# amp_soha_v4.net
KiCad netlist of a schematic drawn in EAGLE
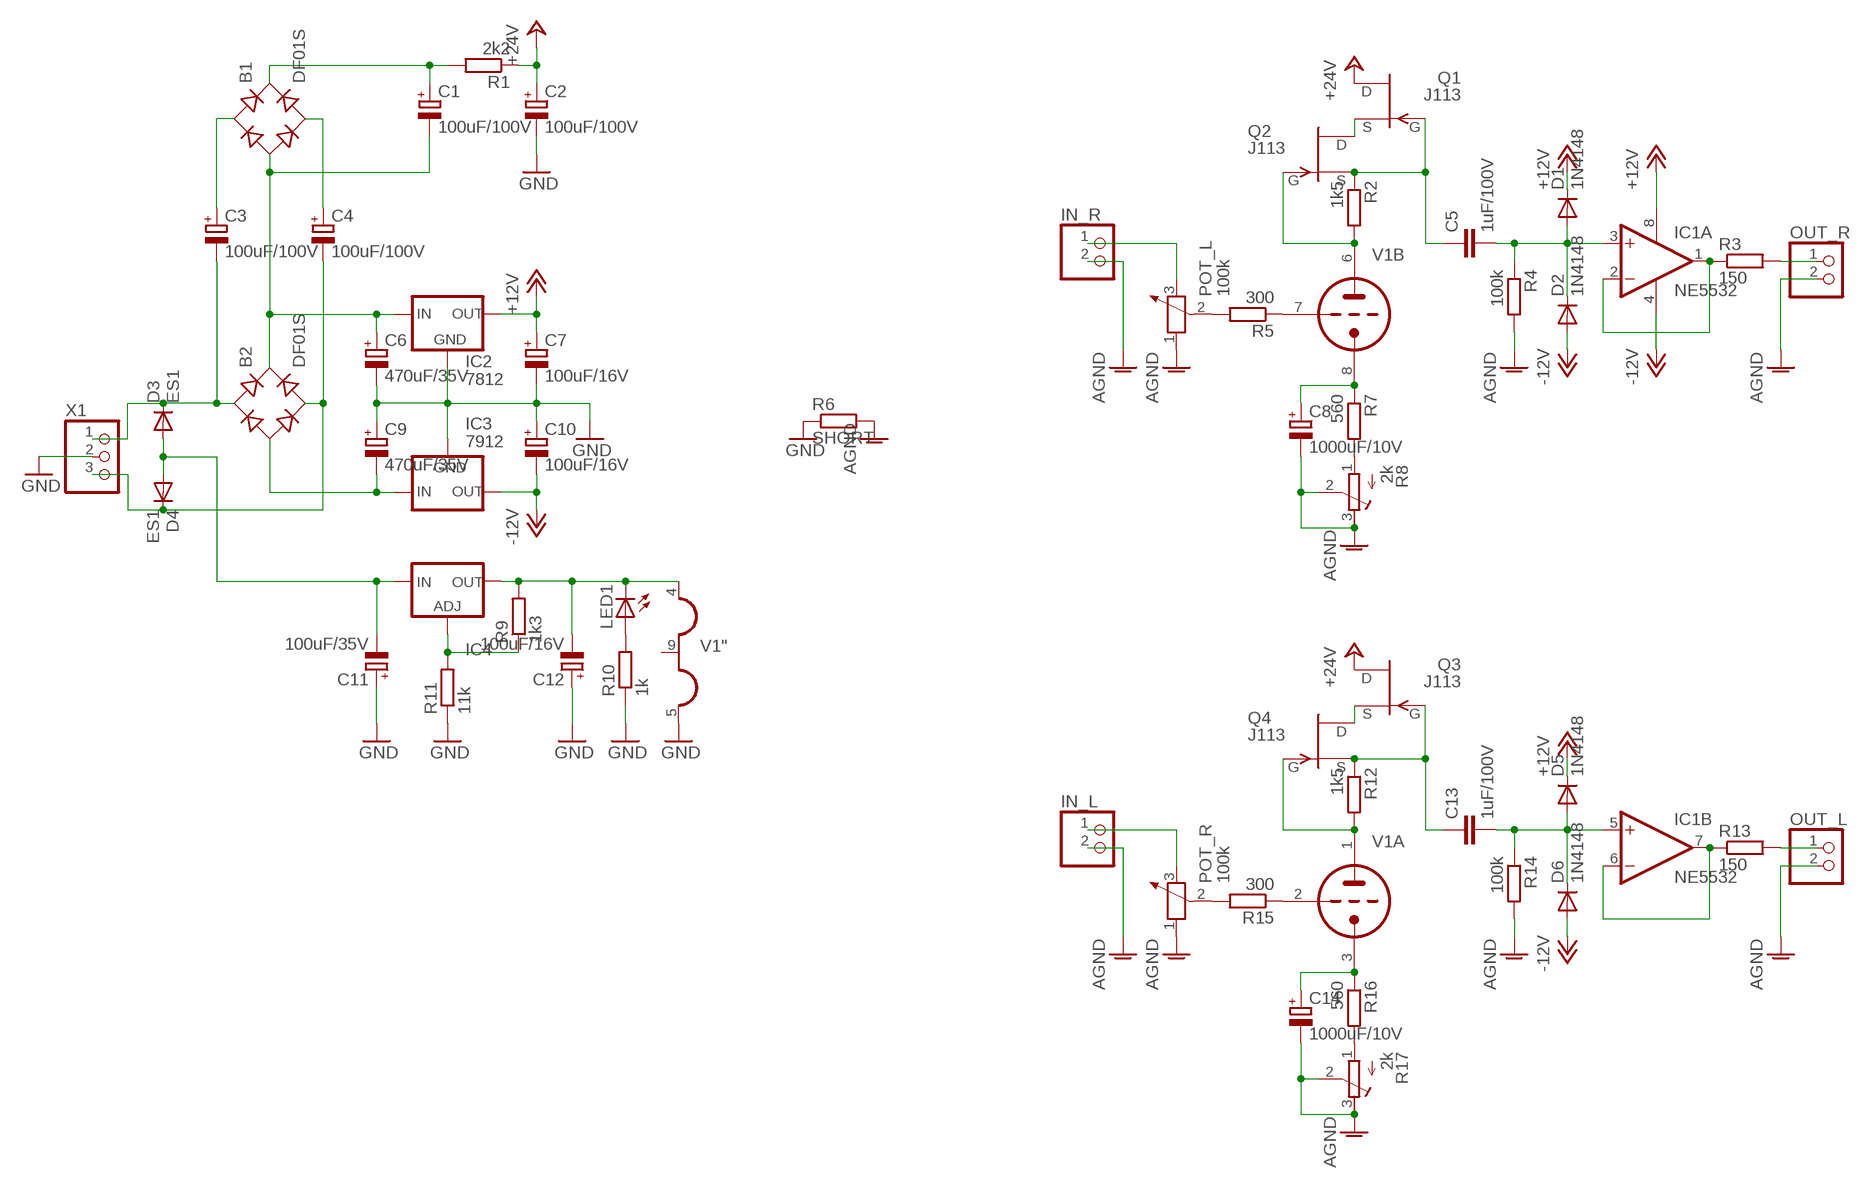
[diagram p0: schematic, sheet 1]

(export (version "E")
  (design (tool "Eeschema 10.0.6"))
  (components
    (comp (ref "B1")
      (value "DF01S")
      (footprint "eagle-import:DFS")
      (libsource (lib "eagle-import") (part "DFS01"))
    )
    (comp (ref "B2")
      (value "DF01S")
      (footprint "eagle-import:DFS")
      (libsource (lib "eagle-import") (part "DFS01"))
    )
    (comp (ref "C1")
      (value "100uF/100V")
      (footprint "eagle-import:E5-10,5")
      (libsource (lib "eagle-import") (part "CPOL-EUE5-10,5"))
    )
    (comp (ref "C2")
      (value "100uF/100V")
      (footprint "eagle-import:E5-10,5")
      (libsource (lib "eagle-import") (part "CPOL-EUE5-10,5"))
    )
    (comp (ref "C3")
      (value "100uF/100V")
      (footprint "eagle-import:E5-10,5")
      (libsource (lib "eagle-import") (part "CPOL-EUE5-10,5"))
    )
    (comp (ref "C4")
      (value "100uF/100V")
      (footprint "eagle-import:E5-10,5")
      (libsource (lib "eagle-import") (part "CPOL-EUE5-10,5"))
    )
    (comp (ref "C5")
      (value "1uF/100V")
      (footprint "eagle-import:C075-052X106")
      (libsource (lib "eagle-import") (part "C-EU075-052X106"))
    )
    (comp (ref "C6")
      (value "470uF/35V")
      (footprint "eagle-import:E5-10,5")
      (libsource (lib "eagle-import") (part "CPOL-EUE5-10,5"))
    )
    (comp (ref "C7")
      (value "100uF/16V")
      (footprint "eagle-import:E2,5-6")
      (libsource (lib "eagle-import") (part "CPOL-EUE2.5-6"))
    )
    (comp (ref "C8")
      (value "1000uF/10V")
      (footprint "eagle-import:E5-10,5")
      (libsource (lib "eagle-import") (part "CPOL-EUE5-10,5"))
    )
    (comp (ref "C9")
      (value "470uF/35V")
      (footprint "eagle-import:E5-10,5")
      (libsource (lib "eagle-import") (part "CPOL-EUE5-10,5"))
    )
    (comp (ref "C10")
      (value "100uF/16V")
      (footprint "eagle-import:E2,5-6")
      (libsource (lib "eagle-import") (part "CPOL-EUE2.5-6"))
    )
    (comp (ref "C11")
      (value "100uF/35V")
      (footprint "eagle-import:E2,5-6")
      (libsource (lib "eagle-import") (part "CPOL-EUE2.5-6"))
    )
    (comp (ref "C12")
      (value "100uF/16V")
      (footprint "eagle-import:E2,5-6")
      (libsource (lib "eagle-import") (part "CPOL-EUE2.5-6"))
    )
    (comp (ref "C13")
      (value "1uF/100V")
      (footprint "eagle-import:C075-052X106")
      (libsource (lib "eagle-import") (part "C-EU075-052X106"))
    )
    (comp (ref "C14")
      (value "1000uF/10V")
      (footprint "eagle-import:E5-10,5")
      (libsource (lib "eagle-import") (part "CPOL-EUE5-10,5"))
    )
    (comp (ref "D1")
      (value "1N4148")
      (footprint "eagle-import:D0805")
      (libsource (lib "eagle-import") (part "1N4148"))
    )
    (comp (ref "D2")
      (value "1N4148")
      (footprint "eagle-import:D0805")
      (libsource (lib "eagle-import") (part "1N4148"))
    )
    (comp (ref "D3")
      (value "ES1")
      (footprint "eagle-import:DO-214AC")
      (libsource (lib "eagle-import") (part "ES1"))
    )
    (comp (ref "D4")
      (value "ES1")
      (footprint "eagle-import:DO-214AC")
      (libsource (lib "eagle-import") (part "ES1"))
    )
    (comp (ref "D5")
      (value "1N4148")
      (footprint "eagle-import:D0805")
      (libsource (lib "eagle-import") (part "1N4148"))
    )
    (comp (ref "D6")
      (value "1N4148")
      (footprint "eagle-import:D0805")
      (libsource (lib "eagle-import") (part "1N4148"))
    )
    (comp (ref "IC1")
      (value "NE5532")
      (footprint "eagle-import:SO08")
      (libsource (lib "eagle-import") (part "NE5535U"))
    )
    (comp (ref "IC2")
      (value "7812")
      (footprint "eagle-import:78XXS")
      (libsource (lib "eagle-import") (part "78XXTO-220"))
    )
    (comp (ref "IC3")
      (value "7912")
      (footprint "eagle-import:79XXS")
      (libsource (lib "eagle-import") (part "79XXTO-220"))
    )
    (comp (ref "IC4")
      (value "LM337TS")
      (footprint "eagle-import:337TS")
      (libsource (lib "eagle-import") (part "LM337TS"))
    )
    (comp (ref "IN_L")
      (value "PINHD-1X2")
      (footprint "eagle-import:1X02")
      (libsource (lib "eagle-import") (part "PINHD-1X2"))
    )
    (comp (ref "IN_R")
      (value "PINHD-1X2")
      (footprint "eagle-import:1X02")
      (libsource (lib "eagle-import") (part "PINHD-1X2"))
    )
    (comp (ref "LED1")
      (value "LED5MM")
      (footprint "eagle-import:LED5MM")
      (libsource (lib "eagle-import") (part "LED5MM"))
    )
    (comp (ref "OUT_L")
      (value "PINHD-1X2")
      (footprint "eagle-import:1X02")
      (libsource (lib "eagle-import") (part "PINHD-1X2"))
    )
    (comp (ref "OUT_R")
      (value "PINHD-1X2")
      (footprint "eagle-import:1X02")
      (libsource (lib "eagle-import") (part "PINHD-1X2"))
    )
    (comp (ref "POT_L")
      (value "100k")
      (footprint "eagle-import:1X03")
      (libsource (lib "eagle-import") (part "POTENTIOMETER_"))
    )
    (comp (ref "POT_R")
      (value "100k")
      (footprint "eagle-import:1X03")
      (libsource (lib "eagle-import") (part "POTENTIOMETER_"))
    )
    (comp (ref "Q1")
      (value "J113")
      (footprint "eagle-import:TO92")
      (libsource (lib "eagle-import") (part "J113"))
    )
    (comp (ref "Q2")
      (value "J113")
      (footprint "eagle-import:TO92")
      (libsource (lib "eagle-import") (part "J113"))
    )
    (comp (ref "Q3")
      (value "J113")
      (footprint "eagle-import:TO92")
      (libsource (lib "eagle-import") (part "J113"))
    )
    (comp (ref "Q4")
      (value "J113")
      (footprint "eagle-import:TO92")
      (libsource (lib "eagle-import") (part "J113"))
    )
    (comp (ref "R1")
      (value "2k2")
      (footprint "eagle-import:R0805")
      (libsource (lib "eagle-import") (part "R-EU_"))
    )
    (comp (ref "R2")
      (value "1k5")
      (footprint "eagle-import:R0805")
      (libsource (lib "eagle-import") (part "R-EU_"))
    )
    (comp (ref "R3")
      (value "150")
      (footprint "eagle-import:R0805")
      (libsource (lib "eagle-import") (part "R-EU_"))
    )
    (comp (ref "R4")
      (value "100k")
      (footprint "eagle-import:R0805")
      (libsource (lib "eagle-import") (part "R-EU_"))
    )
    (comp (ref "R5")
      (value "300")
      (footprint "eagle-import:R0805")
      (libsource (lib "eagle-import") (part "R-EU_"))
    )
    (comp (ref "R6")
      (value "SHORT")
      (footprint "eagle-import:SHORT")
      (libsource (lib "eagle-import") (part "SHORT"))
    )
    (comp (ref "R7")
      (value "560")
      (footprint "eagle-import:R0805")
      (libsource (lib "eagle-import") (part "R-EU_"))
    )
    (comp (ref "R8")
      (value "2k")
      (footprint "eagle-import:RTRIM3296W")
      (libsource (lib "eagle-import") (part "RTRIM329W"))
    )
    (comp (ref "R9")
      (value "1k3")
      (footprint "eagle-import:R0805")
      (libsource (lib "eagle-import") (part "R-EU_"))
    )
    (comp (ref "R10")
      (value "1k")
      (footprint "eagle-import:R0805")
      (libsource (lib "eagle-import") (part "R-EU_"))
    )
    (comp (ref "R11")
      (value "11k")
      (footprint "eagle-import:R0805")
      (libsource (lib "eagle-import") (part "R-EU_"))
    )
    (comp (ref "R12")
      (value "1k5")
      (footprint "eagle-import:R0805")
      (libsource (lib "eagle-import") (part "R-EU_"))
    )
    (comp (ref "R13")
      (value "150")
      (footprint "eagle-import:R0805")
      (libsource (lib "eagle-import") (part "R-EU_"))
    )
    (comp (ref "R14")
      (value "100k")
      (footprint "eagle-import:R0805")
      (libsource (lib "eagle-import") (part "R-EU_"))
    )
    (comp (ref "R15")
      (value "300")
      (footprint "eagle-import:R0805")
      (libsource (lib "eagle-import") (part "R-EU_"))
    )
    (comp (ref "R16")
      (value "560")
      (footprint "eagle-import:R0805")
      (libsource (lib "eagle-import") (part "R-EU_"))
    )
    (comp (ref "R17")
      (value "2k")
      (footprint "eagle-import:RTRIM3296W")
      (libsource (lib "eagle-import") (part "RTRIM329W"))
    )
    (comp (ref "V1")
      (value "12AU7-P")
      (footprint "eagle-import:NOVAL")
      (libsource (lib "eagle-import") (part "12AU7-P"))
    )
    (comp (ref "X1")
      (value "W237-103")
      (footprint "eagle-import:W237-103")
      (libsource (lib "eagle-import") (part "W237-103"))
    )
  )
  (nets
    (net (code "1") (name "+12V") (class "Default")
      (node (ref "C7") (pin "+") (pinfunction "+_+") (pintype "passive"))
      (node (ref "D1") (pin "K") (pinfunction "C_K") (pintype "passive"))
      (node (ref "D5") (pin "K") (pinfunction "C_K") (pintype "passive"))
      (node (ref "IC1") (pin "8") (pinfunction "V+_8") (pintype "power_in"))
      (node (ref "IC2") (pin "OUT") (pinfunction "OUT_OUT") (pintype "passive"))
    )
    (net (code "2") (name "+24V") (class "Default")
      (node (ref "C2") (pin "+") (pinfunction "+_+") (pintype "passive"))
      (node (ref "Q1") (pin "3") (pinfunction "D_3") (pintype "passive"))
      (node (ref "Q3") (pin "3") (pinfunction "D_3") (pintype "passive"))
      (node (ref "R1") (pin "1") (pinfunction "1_1") (pintype "passive"))
    )
    (net (code "3") (name "-12V") (class "Default")
      (node (ref "C10") (pin "-") (pinfunction "-_-") (pintype "passive"))
      (node (ref "D2") (pin "A") (pinfunction "A_A") (pintype "passive"))
      (node (ref "D6") (pin "A") (pinfunction "A_A") (pintype "passive"))
      (node (ref "IC1") (pin "4") (pinfunction "V-_4") (pintype "power_in"))
      (node (ref "IC3") (pin "OUT") (pinfunction "OUT_OUT") (pintype "passive"))
    )
    (net (code "4") (name "AGND") (class "Default")
      (node (ref "C14") (pin "-") (pinfunction "-_-") (pintype "passive"))
      (node (ref "C8") (pin "-") (pinfunction "-_-") (pintype "passive"))
      (node (ref "IN_L") (pin "2") (pinfunction "2_2") (pintype "passive"))
      (node (ref "IN_R") (pin "2") (pinfunction "2_2") (pintype "passive"))
      (node (ref "OUT_L") (pin "2") (pinfunction "2_2") (pintype "passive"))
      (node (ref "OUT_R") (pin "2") (pinfunction "2_2") (pintype "passive"))
      (node (ref "POT_L") (pin "1") (pinfunction "1_1") (pintype "passive"))
      (node (ref "POT_R") (pin "1") (pinfunction "1_1") (pintype "passive"))
      (node (ref "R14") (pin "2") (pinfunction "2_2") (pintype "passive"))
      (node (ref "R17") (pin "2") (pinfunction "S_2") (pintype "passive"))
      (node (ref "R17") (pin "3") (pinfunction "E_3") (pintype "passive"))
      (node (ref "R4") (pin "2") (pinfunction "2_2") (pintype "passive"))
      (node (ref "R6") (pin "2") (pinfunction "2_2") (pintype "passive"))
      (node (ref "R8") (pin "2") (pinfunction "S_2") (pintype "passive"))
      (node (ref "R8") (pin "3") (pinfunction "E_3") (pintype "passive"))
    )
    (net (code "5") (name "GND") (class "Default")
      (node (ref "C10") (pin "+") (pinfunction "+_+") (pintype "passive"))
      (node (ref "C11") (pin "+") (pinfunction "+_+") (pintype "passive"))
      (node (ref "C12") (pin "+") (pinfunction "+_+") (pintype "passive"))
      (node (ref "C2") (pin "-") (pinfunction "-_-") (pintype "passive"))
      (node (ref "C6") (pin "-") (pinfunction "-_-") (pintype "passive"))
      (node (ref "C7") (pin "-") (pinfunction "-_-") (pintype "passive"))
      (node (ref "C9") (pin "+") (pinfunction "+_+") (pintype "passive"))
      (node (ref "IC2") (pin "GND") (pinfunction "GND_GND") (pintype "input"))
      (node (ref "IC3") (pin "GND") (pinfunction "GND_GND") (pintype "input"))
      (node (ref "R10") (pin "1") (pinfunction "1_1") (pintype "passive"))
      (node (ref "R11") (pin "1") (pinfunction "1_1") (pintype "passive"))
      (node (ref "R6") (pin "1") (pinfunction "1_1") (pintype "passive"))
      (node (ref "V1") (pin "5") (pinfunction "H3_5") (pintype "passive"))
      (node (ref "X1") (pin "2") (pinfunction "2_2") (pintype "passive"))
    )
    (net (code "6") (name "Net-(B1-Pad+)") (class "Default")
      (node (ref "B1") (pin "+") (pinfunction "+_+") (pintype "passive"))
      (node (ref "C1") (pin "+") (pinfunction "+_+") (pintype "passive"))
      (node (ref "R1") (pin "2") (pinfunction "2_2") (pintype "passive"))
    )
    (net (code "7") (name "Net-(B1-Pad-)") (class "Default")
      (node (ref "B1") (pin "-") (pinfunction "-_-") (pintype "passive"))
      (node (ref "B2") (pin "+") (pinfunction "+_+") (pintype "passive"))
      (node (ref "C1") (pin "-") (pinfunction "-_-") (pintype "passive"))
      (node (ref "C6") (pin "+") (pinfunction "+_+") (pintype "passive"))
      (node (ref "IC2") (pin "IN") (pinfunction "IN_IN") (pintype "input"))
    )
    (net (code "8") (name "Net-(B1-PadAC1)") (class "Default")
      (node (ref "B1") (pin "AC1") (pinfunction "AC1_AC1") (pintype "passive"))
      (node (ref "C3") (pin "+") (pinfunction "+_+") (pintype "passive"))
    )
    (net (code "9") (name "Net-(B1-PadAC2)") (class "Default")
      (node (ref "B1") (pin "AC2") (pinfunction "AC2_AC2") (pintype "passive"))
      (node (ref "C4") (pin "+") (pinfunction "+_+") (pintype "passive"))
    )
    (net (code "10") (name "Net-(B2-Pad-)") (class "Default")
      (node (ref "B2") (pin "-") (pinfunction "-_-") (pintype "passive"))
      (node (ref "C9") (pin "-") (pinfunction "-_-") (pintype "passive"))
      (node (ref "IC3") (pin "IN") (pinfunction "IN_IN") (pintype "input"))
    )
    (net (code "11") (name "Net-(B2-PadAC1)") (class "Default")
      (node (ref "B2") (pin "AC1") (pinfunction "AC1_AC1") (pintype "passive"))
      (node (ref "C3") (pin "-") (pinfunction "-_-") (pintype "passive"))
      (node (ref "D3") (pin "C") (pinfunction "C_C") (pintype "passive"))
      (node (ref "X1") (pin "1") (pinfunction "1_1") (pintype "passive"))
    )
    (net (code "12") (name "Net-(B2-PadAC2)") (class "Default")
      (node (ref "B2") (pin "AC2") (pinfunction "AC2_AC2") (pintype "passive"))
      (node (ref "C4") (pin "-") (pinfunction "-_-") (pintype "passive"))
      (node (ref "D4") (pin "C") (pinfunction "C_C") (pintype "passive"))
      (node (ref "X1") (pin "3") (pinfunction "3_3") (pintype "passive"))
    )
    (net (code "13") (name "Net-(D2-C)") (class "Default")
      (node (ref "C5") (pin "2") (pinfunction "2_2") (pintype "passive"))
      (node (ref "D1") (pin "A") (pinfunction "A_A") (pintype "passive"))
      (node (ref "D2") (pin "K") (pinfunction "C_K") (pintype "passive"))
      (node (ref "IC1") (pin "3") (pinfunction "+IN_3") (pintype "input"))
      (node (ref "R4") (pin "1") (pinfunction "1_1") (pintype "passive"))
    )
    (net (code "14") (name "Net-(D6-C)") (class "Default")
      (node (ref "C13") (pin "2") (pinfunction "2_2") (pintype "passive"))
      (node (ref "D5") (pin "A") (pinfunction "A_A") (pintype "passive"))
      (node (ref "D6") (pin "K") (pinfunction "C_K") (pintype "passive"))
      (node (ref "IC1") (pin "5") (pinfunction "+IN_5") (pintype "input"))
      (node (ref "R14") (pin "1") (pinfunction "1_1") (pintype "passive"))
    )
    (net (code "15") (name "Net-(IC1A--IN)") (class "Default")
      (node (ref "IC1") (pin "1") (pinfunction "OUT_1") (pintype "output"))
      (node (ref "IC1") (pin "2") (pinfunction "-IN_2") (pintype "input"))
      (node (ref "R3") (pin "1") (pinfunction "1_1") (pintype "passive"))
    )
    (net (code "16") (name "Net-(IC1B--IN)") (class "Default")
      (node (ref "IC1") (pin "6") (pinfunction "-IN_6") (pintype "input"))
      (node (ref "IC1") (pin "7") (pinfunction "OUT_7") (pintype "output"))
      (node (ref "R13") (pin "1") (pinfunction "1_1") (pintype "passive"))
    )
    (net (code "17") (name "Net-(IC4-ADJ)") (class "Default")
      (node (ref "IC4") (pin "1") (pinfunction "ADJ_1") (pintype "input"))
      (node (ref "R11") (pin "2") (pinfunction "2_2") (pintype "passive"))
      (node (ref "R9") (pin "1") (pinfunction "1_1") (pintype "passive"))
    )
    (net (code "18") (name "Net-(IC4-IN)") (class "Default")
      (node (ref "C11") (pin "-") (pinfunction "-_-") (pintype "passive"))
      (node (ref "D3") (pin "A") (pinfunction "A_A") (pintype "passive"))
      (node (ref "D4") (pin "A") (pinfunction "A_A") (pintype "passive"))
      (node (ref "IC4") (pin "2") (pinfunction "IN_2") (pintype "input"))
    )
    (net (code "19") (name "Net-(IC4-OUT)") (class "Default")
      (node (ref "C12") (pin "-") (pinfunction "-_-") (pintype "passive"))
      (node (ref "IC4") (pin "3") (pinfunction "OUT_3") (pintype "passive"))
      (node (ref "LED1") (pin "K") (pinfunction "C_K") (pintype "passive"))
      (node (ref "R9") (pin "2") (pinfunction "2_2") (pintype "passive"))
      (node (ref "V1") (pin "4") (pinfunction "H1_4") (pintype "passive"))
    )
    (net (code "20") (name "Net-(LED1-PadA)") (class "Default")
      (node (ref "LED1") (pin "A") (pinfunction "A_A") (pintype "passive"))
      (node (ref "R10") (pin "2") (pinfunction "2_2") (pintype "passive"))
    )
    (net (code "21") (name "Net-(OUT_L-Pad1)") (class "Default")
      (node (ref "OUT_L") (pin "1") (pinfunction "1_1") (pintype "passive"))
      (node (ref "R13") (pin "2") (pinfunction "2_2") (pintype "passive"))
    )
    (net (code "22") (name "Net-(OUT_R-Pad1)") (class "Default")
      (node (ref "OUT_R") (pin "1") (pinfunction "1_1") (pintype "passive"))
      (node (ref "R3") (pin "2") (pinfunction "2_2") (pintype "passive"))
    )
    (net (code "23") (name "Net-(POT_L-2)") (class "Default")
      (node (ref "IN_R") (pin "1") (pinfunction "1_1") (pintype "passive"))
      (node (ref "POT_L") (pin "3") (pinfunction "2_3") (pintype "passive"))
    )
    (net (code "24") (name "Net-(POT_L-3)") (class "Default")
      (node (ref "POT_L") (pin "2") (pinfunction "3_2") (pintype "passive"))
      (node (ref "R5") (pin "2") (pinfunction "2_2") (pintype "passive"))
    )
    (net (code "25") (name "Net-(POT_R-2)") (class "Default")
      (node (ref "IN_L") (pin "1") (pinfunction "1_1") (pintype "passive"))
      (node (ref "POT_R") (pin "3") (pinfunction "2_3") (pintype "passive"))
    )
    (net (code "26") (name "Net-(POT_R-3)") (class "Default")
      (node (ref "POT_R") (pin "2") (pinfunction "3_2") (pintype "passive"))
      (node (ref "R15") (pin "2") (pinfunction "2_2") (pintype "passive"))
    )
    (net (code "27") (name "Net-(Q1-G)") (class "Default")
      (node (ref "C5") (pin "1") (pinfunction "1_1") (pintype "passive"))
      (node (ref "Q1") (pin "1") (pinfunction "G_1") (pintype "passive"))
      (node (ref "Q2") (pin "2") (pinfunction "S_2") (pintype "passive"))
      (node (ref "R2") (pin "1") (pinfunction "1_1") (pintype "passive"))
    )
    (net (code "28") (name "Net-(Q1-S)") (class "Default")
      (node (ref "Q1") (pin "2") (pinfunction "S_2") (pintype "passive"))
      (node (ref "Q2") (pin "3") (pinfunction "D_3") (pintype "passive"))
    )
    (net (code "29") (name "Net-(Q2-G)") (class "Default")
      (node (ref "Q2") (pin "1") (pinfunction "G_1") (pintype "passive"))
      (node (ref "R2") (pin "2") (pinfunction "2_2") (pintype "passive"))
      (node (ref "V1") (pin "6") (pinfunction "TA_6") (pintype "passive"))
    )
    (net (code "30") (name "Net-(Q3-G)") (class "Default")
      (node (ref "C13") (pin "1") (pinfunction "1_1") (pintype "passive"))
      (node (ref "Q3") (pin "1") (pinfunction "G_1") (pintype "passive"))
      (node (ref "Q4") (pin "2") (pinfunction "S_2") (pintype "passive"))
      (node (ref "R12") (pin "1") (pinfunction "1_1") (pintype "passive"))
    )
    (net (code "31") (name "Net-(Q3-S)") (class "Default")
      (node (ref "Q3") (pin "2") (pinfunction "S_2") (pintype "passive"))
      (node (ref "Q4") (pin "3") (pinfunction "D_3") (pintype "passive"))
    )
    (net (code "32") (name "Net-(Q4-G)") (class "Default")
      (node (ref "Q4") (pin "1") (pinfunction "G_1") (pintype "passive"))
      (node (ref "R12") (pin "2") (pinfunction "2_2") (pintype "passive"))
      (node (ref "V1") (pin "1") (pinfunction "TA_1") (pintype "passive"))
    )
    (net (code "33") (name "Net-(R8-A)") (class "Default")
      (node (ref "R7") (pin "2") (pinfunction "2_2") (pintype "passive"))
      (node (ref "R8") (pin "1") (pinfunction "A_1") (pintype "passive"))
    )
    (net (code "34") (name "Net-(R17-A)") (class "Default")
      (node (ref "R16") (pin "2") (pinfunction "2_2") (pintype "passive"))
      (node (ref "R17") (pin "1") (pinfunction "A_1") (pintype "passive"))
    )
    (net (code "35") (name "Net-(V1B-TG)") (class "Default")
      (node (ref "R15") (pin "1") (pinfunction "1_1") (pintype "passive"))
      (node (ref "V1") (pin "2") (pinfunction "TG_2") (pintype "passive"))
    )
    (net (code "36") (name "Net-(V1B-TK)") (class "Default")
      (node (ref "C14") (pin "+") (pinfunction "+_+") (pintype "passive"))
      (node (ref "R16") (pin "1") (pinfunction "1_1") (pintype "passive"))
      (node (ref "V1") (pin "3") (pinfunction "TK_3") (pintype "passive"))
    )
    (net (code "37") (name "Net-(V1C-TG)") (class "Default")
      (node (ref "R5") (pin "1") (pinfunction "1_1") (pintype "passive"))
      (node (ref "V1") (pin "7") (pinfunction "TG_7") (pintype "passive"))
    )
    (net (code "38") (name "Net-(V1C-TK)") (class "Default")
      (node (ref "C8") (pin "+") (pinfunction "+_+") (pintype "passive"))
      (node (ref "R7") (pin "1") (pinfunction "1_1") (pintype "passive"))
      (node (ref "V1") (pin "8") (pinfunction "TK_8") (pintype "passive"))
    )
    (net (code "39") (name "unconnected-(V1A-H2-Pad9)") (class "Default")
      (node (ref "V1") (pin "9") (pinfunction "H2_9") (pintype "passive"))
    )
  )
)
